# Sensors.net
KiCad netlist of a schematic drawn in Altium Designer
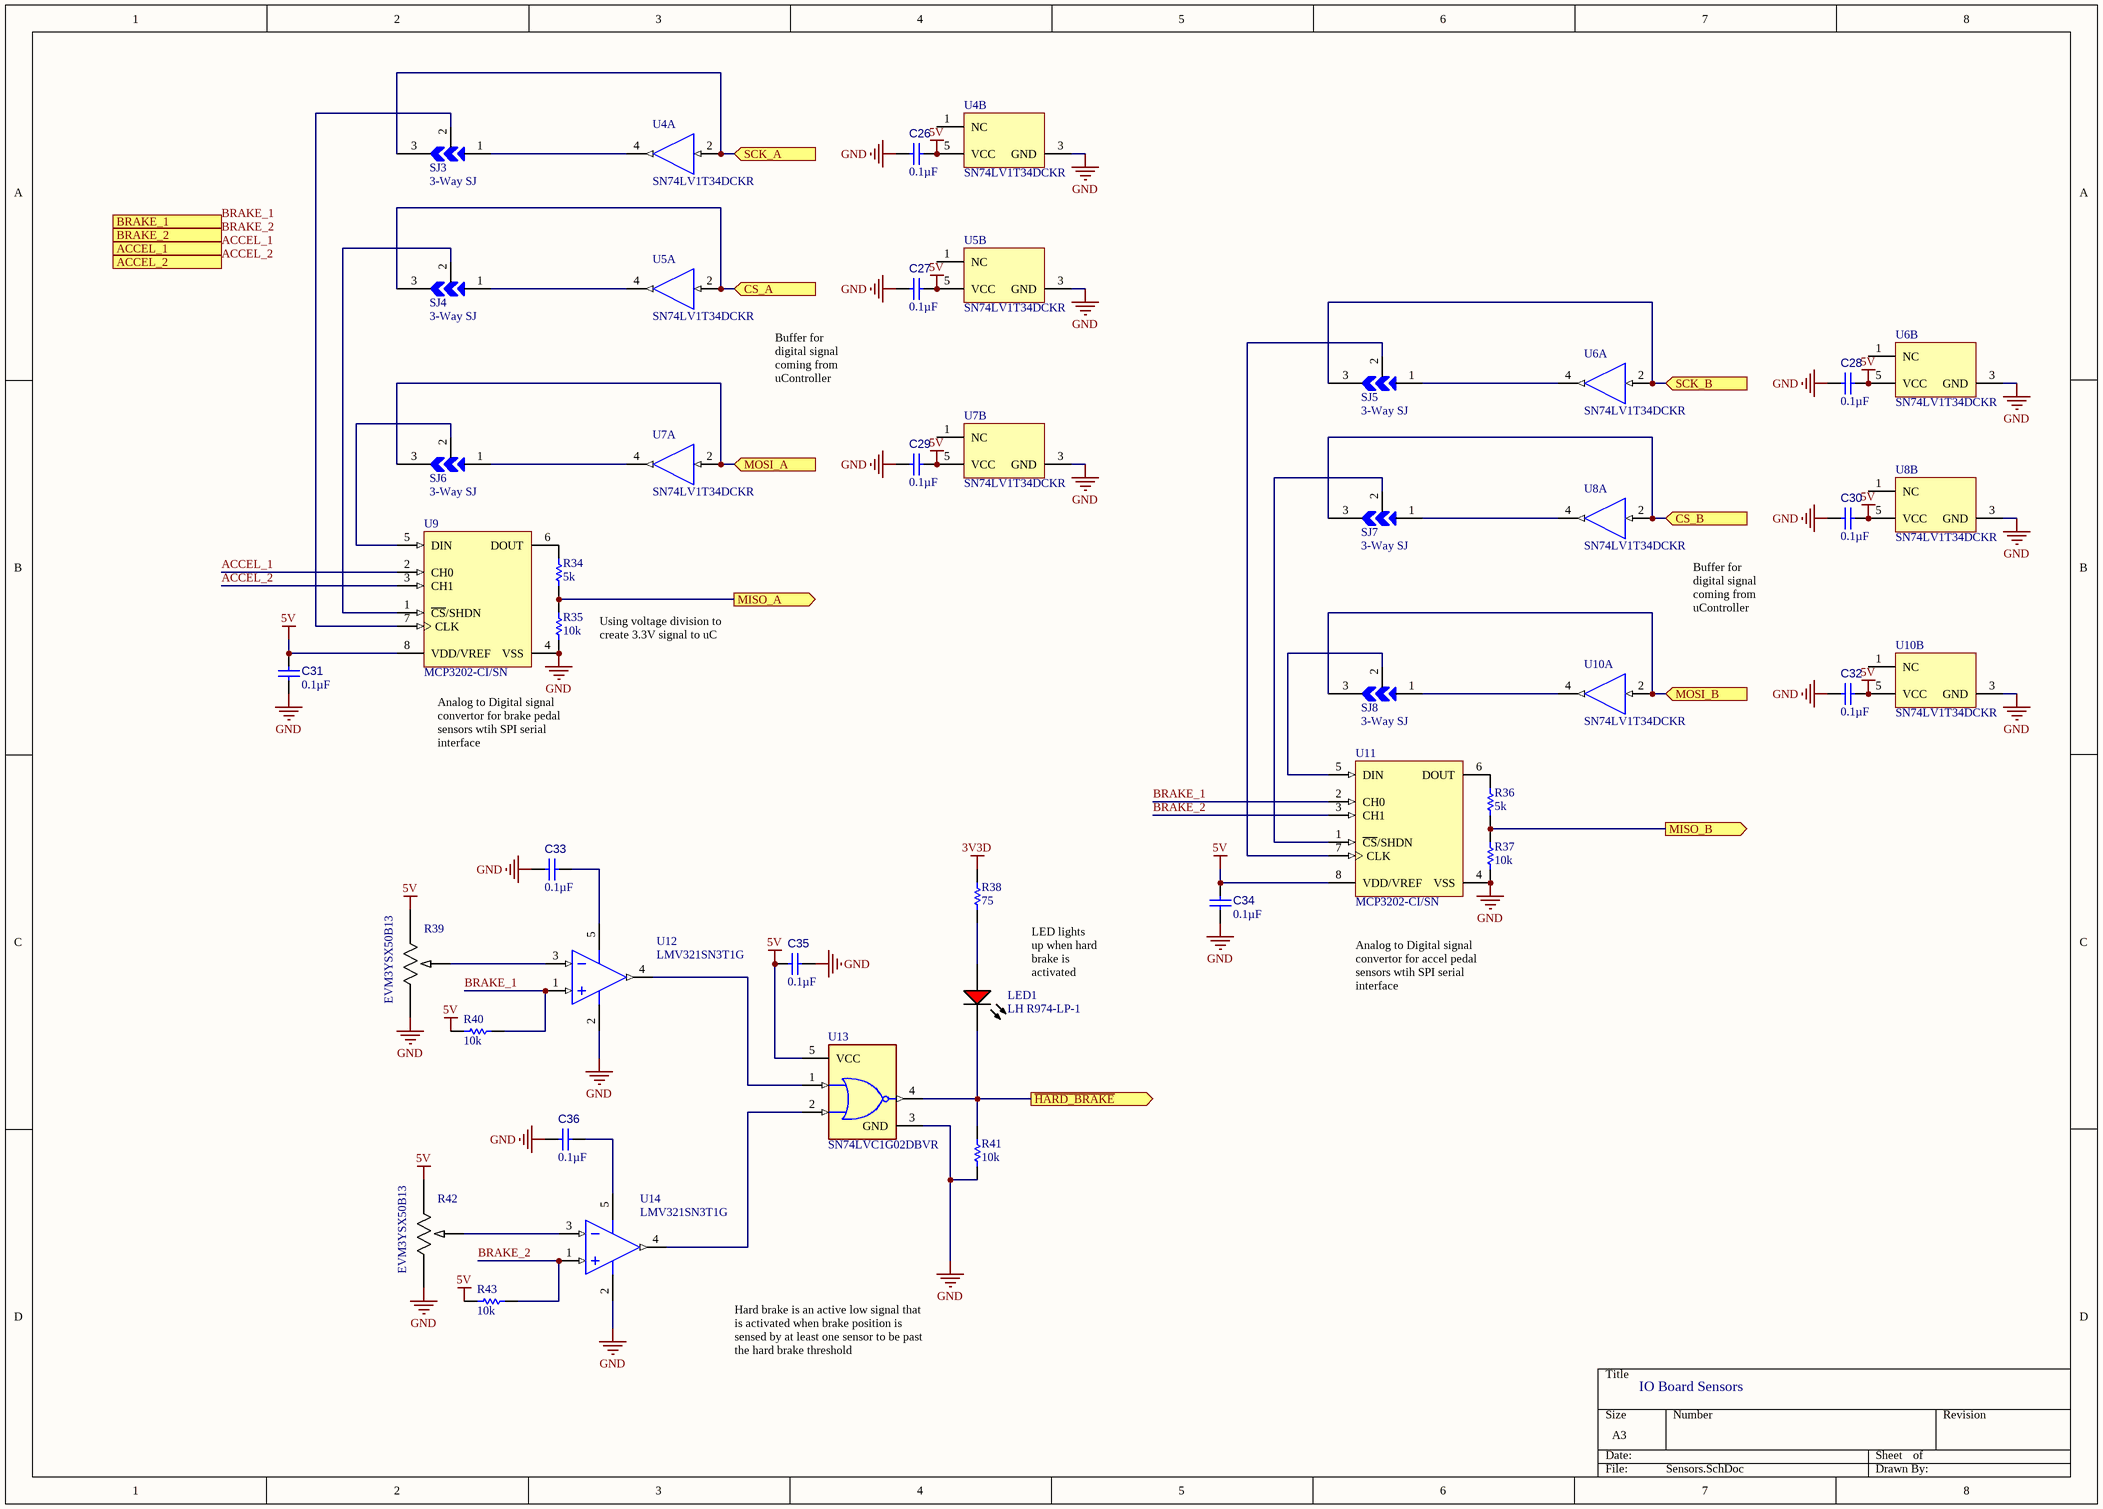
[diagram p0: Sensors.SchDoc]

(export (version "E")
  (design (tool "Eeschema 10.0.6"))
  (components
    (comp (ref "C26")
      (value "0.1µF")
      (footprint "CAPC2013X145X50ML20T25")
      (description "Chip Capacitor, 0.1 uF, +/-10%, 25 V, 0805 (2012 Metric)")
      (fields
        (field (name "MANUFACTURER") "KEMET")
        (field (name "MANUFACTURER PART NUMBER") "C0805C104K3RACTU")
      )
      (libsource (lib "Caltech FSAE") (part "CAP-NP-2"))
    )
    (comp (ref "C27")
      (value "0.1µF")
      (footprint "CAPC2013X145X50ML20T25")
      (description "Chip Capacitor, 0.1 uF, +/-10%, 25 V, 0805 (2012 Metric)")
      (fields
        (field (name "MANUFACTURER") "KEMET")
        (field (name "MANUFACTURER PART NUMBER") "C0805C104K3RACTU")
      )
      (libsource (lib "Caltech FSAE") (part "CAP-NP-2"))
    )
    (comp (ref "C28")
      (value "0.1µF")
      (footprint "CAPC2013X145X50ML20T25")
      (description "Chip Capacitor, 0.1 uF, +/-10%, 25 V, 0805 (2012 Metric)")
      (fields
        (field (name "MANUFACTURER") "KEMET")
        (field (name "MANUFACTURER PART NUMBER") "C0805C104K3RACTU")
      )
      (libsource (lib "Caltech FSAE") (part "CAP-NP-2"))
    )
    (comp (ref "C29")
      (value "0.1µF")
      (footprint "CAPC2013X145X50ML20T25")
      (description "Chip Capacitor, 0.1 uF, +/-10%, 25 V, 0805 (2012 Metric)")
      (fields
        (field (name "MANUFACTURER") "KEMET")
        (field (name "MANUFACTURER PART NUMBER") "C0805C104K3RACTU")
      )
      (libsource (lib "Caltech FSAE") (part "CAP-NP-2"))
    )
    (comp (ref "C30")
      (value "0.1µF")
      (footprint "CAPC2013X145X50ML20T25")
      (description "Chip Capacitor, 0.1 uF, +/-10%, 25 V, 0805 (2012 Metric)")
      (fields
        (field (name "MANUFACTURER") "KEMET")
        (field (name "MANUFACTURER PART NUMBER") "C0805C104K3RACTU")
      )
      (libsource (lib "Caltech FSAE") (part "CAP-NP-2"))
    )
    (comp (ref "C31")
      (value "0.1µF")
      (footprint "CAPC2013X145X50ML20T25")
      (description "Chip Capacitor, 0.1 uF, +/-10%, 25 V, 0805 (2012 Metric)")
      (fields
        (field (name "MANUFACTURER") "KEMET")
        (field (name "MANUFACTURER PART NUMBER") "C0805C104K3RACTU")
      )
      (libsource (lib "Caltech FSAE") (part "CAP-NP-2"))
    )
    (comp (ref "C32")
      (value "0.1µF")
      (footprint "CAPC2013X145X50ML20T25")
      (description "Chip Capacitor, 0.1 uF, +/-10%, 25 V, 0805 (2012 Metric)")
      (fields
        (field (name "MANUFACTURER") "KEMET")
        (field (name "MANUFACTURER PART NUMBER") "C0805C104K3RACTU")
      )
      (libsource (lib "Caltech FSAE") (part "CAP-NP-2"))
    )
    (comp (ref "C33")
      (value "0.1µF")
      (footprint "CAPC2013X145X50ML20T25")
      (description "Chip Capacitor, 0.1 uF, +/-10%, 25 V, 0805 (2012 Metric)")
      (fields
        (field (name "MANUFACTURER") "KEMET")
        (field (name "MANUFACTURER PART NUMBER") "C0805C104K3RACTU")
      )
      (libsource (lib "Caltech FSAE") (part "CAP-NP-2"))
    )
    (comp (ref "C34")
      (value "0.1µF")
      (footprint "CAPC2013X145X50ML20T25")
      (description "Chip Capacitor, 0.1 uF, +/-10%, 25 V, 0805 (2012 Metric)")
      (fields
        (field (name "MANUFACTURER") "KEMET")
        (field (name "MANUFACTURER PART NUMBER") "C0805C104K3RACTU")
      )
      (libsource (lib "Caltech FSAE") (part "CAP-NP-2"))
    )
    (comp (ref "C35")
      (value "0.1µF")
      (footprint "CAPC2013X145X50ML20T25")
      (description "Chip Capacitor, 0.1 uF, +/-10%, 25 V, 0805 (2012 Metric)")
      (fields
        (field (name "MANUFACTURER") "KEMET")
        (field (name "MANUFACTURER PART NUMBER") "C0805C104K3RACTU")
      )
      (libsource (lib "Caltech FSAE") (part "CAP-NP-2"))
    )
    (comp (ref "C36")
      (value "0.1µF")
      (footprint "CAPC2013X145X50ML20T25")
      (description "Chip Capacitor, 0.1 uF, +/-10%, 25 V, 0805 (2012 Metric)")
      (fields
        (field (name "MANUFACTURER") "KEMET")
        (field (name "MANUFACTURER PART NUMBER") "C0805C104K3RACTU")
      )
      (libsource (lib "Caltech FSAE") (part "CAP-NP-2"))
    )
    (comp (ref "LED1")
      (value "LH R974-LP-1")
      (footprint "0805_A")
      (description "LED RED DIFFUSED 0805 SMD")
      (libsource (lib "uControllerTemplate2021") (part "CMP-62016-000032-1"))
    )
    (comp (ref "R34")
      (value "5k")
      (footprint "RESC2013X50X35ML15T15")
      (description "Chip Resistor, 10k Ohm, +/- 1%, 125 mW, -55 to 155 degC, 0805 (2012 Metric)")
      (fields
        (field (name "MANUFACTURER") "Panasonic")
        (field (name "MANUFACTURER PART NUMBER") "ERA-6AEB4991V")
      )
      (libsource (lib "Caltech FSAE") (part "RES-2"))
    )
    (comp (ref "R35")
      (value "10k")
      (footprint "RESC2013X50X35ML15T15")
      (description "Chip Resistor, 10k Ohm, +/- 1%, 125 mW, -55 to 155 degC, 0805 (2012 Metric)")
      (fields
        (field (name "MANUFACTURER") "Yageo")
        (field (name "MANUFACTURER PART NUMBER") "RC0805FR-0710KL")
      )
      (libsource (lib "Caltech FSAE") (part "RES-2"))
    )
    (comp (ref "R36")
      (value "5k")
      (footprint "RESC2013X50X35ML15T15")
      (description "Chip Resistor, 10k Ohm, +/- 1%, 125 mW, -55 to 155 degC, 0805 (2012 Metric)")
      (fields
        (field (name "MANUFACTURER") "Panasonic")
        (field (name "MANUFACTURER PART NUMBER") "ERA-6AEB4991V")
      )
      (libsource (lib "Caltech FSAE") (part "RES-2"))
    )
    (comp (ref "R37")
      (value "10k")
      (footprint "RESC2013X50X35ML15T15")
      (description "Chip Resistor, 10k Ohm, +/- 1%, 125 mW, -55 to 155 degC, 0805 (2012 Metric)")
      (fields
        (field (name "MANUFACTURER") "Yageo")
        (field (name "MANUFACTURER PART NUMBER") "RC0805FR-0710KL")
      )
      (libsource (lib "Caltech FSAE") (part "RES-2"))
    )
    (comp (ref "R38")
      (value "75")
      (footprint "RESC2013X50X35ML15T15")
      (description "Chip Resistor, 10k Ohm, +/- 1%, 125 mW, -55 to 155 degC, 0805 (2012 Metric)")
      (fields
        (field (name "MANUFACTURER") "Panasonic")
        (field (name "MANUFACTURER PART NUMBER") "ERA-6AEB750V")
      )
      (libsource (lib "Caltech FSAE") (part "RES-2"))
    )
    (comp (ref "R39")
      (value "EVM3YSX50B13")
      (footprint "POT_EVM3Y_PAN")
      (description "Panasonic EVM-3YSX50B13")
      (fields (field (name "COPYRIGHT") "Copyright (C) 2018 Accelerated Designs. All rights reserved"))
      (libsource (lib "IO_Board") (part "EVM3YSX50B13"))
    )
    (comp (ref "R40")
      (value "10k")
      (footprint "RESC2013X50X35ML15T15")
      (description "Chip Resistor, 10k Ohm, +/- 1%, 125 mW, -55 to 155 degC, 0805 (2012 Metric)")
      (fields
        (field (name "MANUFACTURER") "Yageo")
        (field (name "MANUFACTURER PART NUMBER") "RC0805FR-0710KL")
      )
      (libsource (lib "Caltech FSAE") (part "RES-2"))
    )
    (comp (ref "R41")
      (value "10k")
      (footprint "RESC2013X50X35ML15T15")
      (description "Chip Resistor, 10k Ohm, +/- 1%, 125 mW, -55 to 155 degC, 0805 (2012 Metric)")
      (fields
        (field (name "MANUFACTURER") "Yageo")
        (field (name "MANUFACTURER PART NUMBER") "RC0805FR-0710KL")
      )
      (libsource (lib "Caltech FSAE") (part "RES-2"))
    )
    (comp (ref "R42")
      (value "EVM3YSX50B13")
      (footprint "POT_EVM3Y_PAN")
      (description "Panasonic EVM-3YSX50B13")
      (fields (field (name "COPYRIGHT") "Copyright (C) 2018 Accelerated Designs. All rights reserved"))
      (libsource (lib "IO_Board") (part "EVM3YSX50B13"))
    )
    (comp (ref "R43")
      (value "10k")
      (footprint "RESC2013X50X35ML15T15")
      (description "Chip Resistor, 10k Ohm, +/- 1%, 125 mW, -55 to 155 degC, 0805 (2012 Metric)")
      (fields
        (field (name "MANUFACTURER") "Yageo")
        (field (name "MANUFACTURER PART NUMBER") "RC0805FR-0710KL")
      )
      (libsource (lib "Caltech FSAE") (part "RES-2"))
    )
    (comp (ref "SJ3")
      (value "3-Way SJ")
      (footprint "3-Way SJ")
      (description "3-Way Solder Jumper")
      (libsource (lib "uControllerTemplate2021") (part "3-Way SJ"))
    )
    (comp (ref "SJ4")
      (value "3-Way SJ")
      (footprint "3-Way SJ")
      (description "3-Way Solder Jumper")
      (libsource (lib "uControllerTemplate2021") (part "3-Way SJ"))
    )
    (comp (ref "SJ5")
      (value "3-Way SJ")
      (footprint "3-Way SJ")
      (description "3-Way Solder Jumper")
      (libsource (lib "uControllerTemplate2021") (part "3-Way SJ"))
    )
    (comp (ref "SJ6")
      (value "3-Way SJ")
      (footprint "3-Way SJ")
      (description "3-Way Solder Jumper")
      (libsource (lib "uControllerTemplate2021") (part "3-Way SJ"))
    )
    (comp (ref "SJ7")
      (value "3-Way SJ")
      (footprint "3-Way SJ")
      (description "3-Way Solder Jumper")
      (libsource (lib "uControllerTemplate2021") (part "3-Way SJ"))
    )
    (comp (ref "SJ8")
      (value "3-Way SJ")
      (footprint "3-Way SJ")
      (description "3-Way Solder Jumper")
      (libsource (lib "uControllerTemplate2021") (part "3-Way SJ"))
    )
    (comp (ref "U4")
      (value "SN74LV1T34DCKR")
      (footprint "DCK0005A_L")
      (description "Single Power Supply BUFFER Logic Level Shifter (no enable), DCK0005A, LARGE T&R")
      (fields
        (field (name "MANUFACTURER") "Texas Instruments")
        (field (name "GENERIC PART NUMBER") "SN74LV1T34")
      )
      (libsource (lib "Altium Content Vault") (part "TI-SN74XXX1XXX-XX-5"))
    )
    (comp (ref "U5")
      (value "SN74LV1T34DCKR")
      (footprint "DCK0005A_L")
      (description "Single Power Supply BUFFER Logic Level Shifter (no enable), DCK0005A, LARGE T&R")
      (fields
        (field (name "MANUFACTURER") "Texas Instruments")
        (field (name "GENERIC PART NUMBER") "SN74LV1T34")
      )
      (libsource (lib "Altium Content Vault") (part "TI-SN74XXX1XXX-XX-5"))
    )
    (comp (ref "U6")
      (value "SN74LV1T34DCKR")
      (footprint "DCK0005A_L")
      (description "Single Power Supply BUFFER Logic Level Shifter (no enable), DCK0005A, LARGE T&R")
      (fields
        (field (name "MANUFACTURER") "Texas Instruments")
        (field (name "GENERIC PART NUMBER") "SN74LV1T34")
      )
      (libsource (lib "") (part "TI-SN74XXX1XXX-XX-5_1"))
    )
    (comp (ref "U7")
      (value "SN74LV1T34DCKR")
      (footprint "DCK0005A_L")
      (description "Single Power Supply BUFFER Logic Level Shifter (no enable), DCK0005A, LARGE T&R")
      (fields
        (field (name "MANUFACTURER") "Texas Instruments")
        (field (name "GENERIC PART NUMBER") "SN74LV1T34")
      )
      (libsource (lib "") (part "TI-SN74XXX1XXX-XX-5_1"))
    )
    (comp (ref "U8")
      (value "SN74LV1T34DCKR")
      (footprint "DCK0005A_L")
      (description "Single Power Supply BUFFER Logic Level Shifter (no enable), DCK0005A, LARGE T&R")
      (fields
        (field (name "MANUFACTURER") "Texas Instruments")
        (field (name "GENERIC PART NUMBER") "SN74LV1T34")
      )
      (libsource (lib "Altium Content Vault") (part "TI-SN74XXX1XXX-XX-5"))
    )
    (comp (ref "U9")
      (value "MCP3202-CI/SN")
      (footprint "SOIC-SN8_L")
      (libsource (lib "Altium Content Vault") (part "CON-ADC-MCP3002-8"))
    )
    (comp (ref "U10")
      (value "SN74LV1T34DCKR")
      (footprint "DCK0005A_L")
      (description "Single Power Supply BUFFER Logic Level Shifter (no enable), DCK0005A, LARGE T&R")
      (fields
        (field (name "MANUFACTURER") "Texas Instruments")
        (field (name "GENERIC PART NUMBER") "SN74LV1T34")
      )
      (libsource (lib "Altium Content Vault") (part "TI-SN74XXX1XXX-XX-5"))
    )
    (comp (ref "U11")
      (value "MCP3202-CI/SN")
      (footprint "SOIC-SN8_L")
      (libsource (lib "Altium Content Vault") (part "CON-ADC-MCP3002-8"))
    )
    (comp (ref "U12")
      (value "LMV321SN3T1G")
      (footprint "ONSC-TSOP-5-483-02_V")
      (fields (field (name "MANUFACTURER") "On Semiconductor"))
      (libsource (lib "Altium Content Vault") (part "ONSC-LMV321-TSOP-5-483-02"))
    )
    (comp (ref "U13")
      (value "SN74LVC1G02DBVR")
      (footprint "FP-DBV0005A-MFG")
      (description "IC GATE NOR 1CH 2-INP SOT23-5")
      (fields
        (field (name "OCTOPART") "https://octopart.com/sn74lvc1g02dbvr-texas+instruments-464409")
        (field (name "MANUFACTURER") "Texas Instruments")
      )
      (libsource (lib "Altium Content Vault") (part "8be38c0101a6f76b12a6e3a542e29a9"))
    )
    (comp (ref "U14")
      (value "LMV321SN3T1G")
      (footprint "ONSC-TSOP-5-483-02_V")
      (fields (field (name "MANUFACTURER") "On Semiconductor"))
      (libsource (lib "Altium Content Vault") (part "ONSC-LMV321-TSOP-5-483-02"))
    )
  )
  (nets
    (net (code "1") (name "/ACCEL_1") (class "Default")
      (node (ref "U9") (pin "2") (pinfunction "CH0_2") (pintype "input"))
    )
    (net (code "2") (name "/ACCEL_2") (class "Default")
      (node (ref "U9") (pin "3") (pinfunction "CH1_3") (pintype "input"))
    )
    (net (code "3") (name "/BRAKE_1") (class "Default")
      (node (ref "R40") (pin "1") (pinfunction "1_1") (pintype "passive"))
      (node (ref "U11") (pin "2") (pinfunction "CH0_2") (pintype "input"))
      (node (ref "U12") (pin "1") (pinfunction "IN+_1") (pintype "input"))
    )
    (net (code "4") (name "/BRAKE_2") (class "Default")
      (node (ref "R43") (pin "1") (pinfunction "1_1") (pintype "passive"))
      (node (ref "U11") (pin "3") (pinfunction "CH1_3") (pintype "input"))
      (node (ref "U14") (pin "1") (pinfunction "IN+_1") (pintype "input"))
    )
    (net (code "5") (name "/CS_A") (class "Default")
      (node (ref "SJ4") (pin "3") (pinfunction "3_3") (pintype "passive"))
      (node (ref "U5") (pin "2") (pinfunction "A_2") (pintype "input"))
    )
    (net (code "6") (name "/CS_B") (class "Default")
      (node (ref "SJ7") (pin "3") (pinfunction "3_3") (pintype "passive"))
      (node (ref "U8") (pin "2") (pinfunction "A_2") (pintype "input"))
    )
    (net (code "7") (name "/MISO_A") (class "Default")
      (node (ref "R34") (pin "2") (pinfunction "2_2") (pintype "passive"))
      (node (ref "R35") (pin "2") (pinfunction "2_2") (pintype "passive"))
    )
    (net (code "8") (name "/MISO_B") (class "Default")
      (node (ref "R36") (pin "2") (pinfunction "2_2") (pintype "passive"))
      (node (ref "R37") (pin "2") (pinfunction "2_2") (pintype "passive"))
    )
    (net (code "9") (name "/MOSI_A") (class "Default")
      (node (ref "SJ6") (pin "3") (pinfunction "3_3") (pintype "passive"))
      (node (ref "U7") (pin "2") (pinfunction "A_2") (pintype "input"))
    )
    (net (code "10") (name "/MOSI_B") (class "Default")
      (node (ref "SJ8") (pin "3") (pinfunction "3_3") (pintype "passive"))
      (node (ref "U10") (pin "2") (pinfunction "A_2") (pintype "input"))
    )
    (net (code "11") (name "/SCK_A") (class "Default")
      (node (ref "SJ3") (pin "3") (pinfunction "3_3") (pintype "passive"))
      (node (ref "U4") (pin "2") (pinfunction "A_2") (pintype "input"))
    )
    (net (code "12") (name "/SCK_B") (class "Default")
      (node (ref "SJ5") (pin "3") (pinfunction "3_3") (pintype "passive"))
      (node (ref "U6") (pin "2") (pinfunction "A_2") (pintype "input"))
    )
    (net (code "13") (name "/~{HARD_BRAKE}") (class "Default")
      (node (ref "LED1") (pin "1") (pinfunction "K_1") (pintype "passive"))
      (node (ref "R41") (pin "2") (pinfunction "2_2") (pintype "passive"))
      (node (ref "U13") (pin "4") (pinfunction "Y_4") (pintype "output"))
    )
    (net (code "14") (name "3V3D") (class "Default")
      (node (ref "R38") (pin "1") (pinfunction "1_1") (pintype "passive"))
    )
    (net (code "15") (name "5V") (class "Default")
      (node (ref "C26") (pin "1") (pinfunction "1_1") (pintype "passive"))
      (node (ref "C27") (pin "1") (pinfunction "1_1") (pintype "passive"))
      (node (ref "C28") (pin "1") (pinfunction "1_1") (pintype "passive"))
      (node (ref "C29") (pin "1") (pinfunction "1_1") (pintype "passive"))
      (node (ref "C30") (pin "1") (pinfunction "1_1") (pintype "passive"))
      (node (ref "C31") (pin "2") (pinfunction "2_2") (pintype "passive"))
      (node (ref "C32") (pin "1") (pinfunction "1_1") (pintype "passive"))
      (node (ref "C34") (pin "2") (pinfunction "2_2") (pintype "passive"))
      (node (ref "C35") (pin "2") (pinfunction "2_2") (pintype "passive"))
      (node (ref "R39") (pin "1") (pinfunction "1_1") (pintype "passive"))
      (node (ref "R40") (pin "2") (pinfunction "2_2") (pintype "passive"))
      (node (ref "R42") (pin "1") (pinfunction "1_1") (pintype "passive"))
      (node (ref "R43") (pin "2") (pinfunction "2_2") (pintype "passive"))
      (node (ref "U10") (pin "5") (pinfunction "VCC_5") (pintype "power_in"))
      (node (ref "U11") (pin "8") (pinfunction "VDD/VREF_8") (pintype "power_in"))
      (node (ref "U13") (pin "5") (pinfunction "VCC_5") (pintype "power_in"))
      (node (ref "U4") (pin "5") (pinfunction "VCC_5") (pintype "power_in"))
      (node (ref "U5") (pin "5") (pinfunction "VCC_5") (pintype "power_in"))
      (node (ref "U6") (pin "5") (pinfunction "VCC_5") (pintype "power_in"))
      (node (ref "U7") (pin "5") (pinfunction "VCC_5") (pintype "power_in"))
      (node (ref "U8") (pin "5") (pinfunction "VCC_5") (pintype "power_in"))
      (node (ref "U9") (pin "8") (pinfunction "VDD/VREF_8") (pintype "power_in"))
    )
    (net (code "16") (name "GND") (class "Default")
      (node (ref "C26") (pin "2") (pinfunction "2_2") (pintype "passive"))
      (node (ref "C27") (pin "2") (pinfunction "2_2") (pintype "passive"))
      (node (ref "C28") (pin "2") (pinfunction "2_2") (pintype "passive"))
      (node (ref "C29") (pin "2") (pinfunction "2_2") (pintype "passive"))
      (node (ref "C30") (pin "2") (pinfunction "2_2") (pintype "passive"))
      (node (ref "C31") (pin "1") (pinfunction "1_1") (pintype "passive"))
      (node (ref "C32") (pin "2") (pinfunction "2_2") (pintype "passive"))
      (node (ref "C33") (pin "2") (pinfunction "2_2") (pintype "passive"))
      (node (ref "C34") (pin "1") (pinfunction "1_1") (pintype "passive"))
      (node (ref "C35") (pin "1") (pinfunction "1_1") (pintype "passive"))
      (node (ref "C36") (pin "2") (pinfunction "2_2") (pintype "passive"))
      (node (ref "R35") (pin "1") (pinfunction "1_1") (pintype "passive"))
      (node (ref "R37") (pin "1") (pinfunction "1_1") (pintype "passive"))
      (node (ref "R39") (pin "3") (pinfunction "3_3") (pintype "passive"))
      (node (ref "R41") (pin "1") (pinfunction "1_1") (pintype "passive"))
      (node (ref "R42") (pin "3") (pinfunction "3_3") (pintype "passive"))
      (node (ref "U10") (pin "3") (pinfunction "GND_3") (pintype "power_in"))
      (node (ref "U11") (pin "4") (pinfunction "VSS_4") (pintype "power_in"))
      (node (ref "U12") (pin "2") (pinfunction "V-_2") (pintype "power_in"))
      (node (ref "U13") (pin "3") (pinfunction "GND_3") (pintype "power_in"))
      (node (ref "U14") (pin "2") (pinfunction "V-_2") (pintype "power_in"))
      (node (ref "U4") (pin "3") (pinfunction "GND_3") (pintype "power_in"))
      (node (ref "U5") (pin "3") (pinfunction "GND_3") (pintype "power_in"))
      (node (ref "U6") (pin "3") (pinfunction "GND_3") (pintype "power_in"))
      (node (ref "U7") (pin "3") (pinfunction "GND_3") (pintype "power_in"))
      (node (ref "U8") (pin "3") (pinfunction "GND_3") (pintype "power_in"))
      (node (ref "U9") (pin "4") (pinfunction "VSS_4") (pintype "power_in"))
    )
    (net (code "17") (name "Net-(LED1-A)") (class "Default")
      (node (ref "LED1") (pin "2") (pinfunction "A_2") (pintype "passive"))
      (node (ref "R38") (pin "2") (pinfunction "2_2") (pintype "passive"))
    )
    (net (code "18") (name "Net-(U4A-Y)") (class "Default")
      (node (ref "SJ3") (pin "1") (pinfunction "1_1") (pintype "passive"))
      (node (ref "U4") (pin "4") (pinfunction "Y_4") (pintype "output"))
    )
    (net (code "19") (name "Net-(U5A-Y)") (class "Default")
      (node (ref "SJ4") (pin "1") (pinfunction "1_1") (pintype "passive"))
      (node (ref "U5") (pin "4") (pinfunction "Y_4") (pintype "output"))
    )
    (net (code "20") (name "Net-(U6A-Y)") (class "Default")
      (node (ref "SJ5") (pin "1") (pinfunction "1_1") (pintype "passive"))
      (node (ref "U6") (pin "4") (pinfunction "Y_4") (pintype "output"))
    )
    (net (code "21") (name "Net-(U7A-Y)") (class "Default")
      (node (ref "SJ6") (pin "1") (pinfunction "1_1") (pintype "passive"))
      (node (ref "U7") (pin "4") (pinfunction "Y_4") (pintype "output"))
    )
    (net (code "22") (name "Net-(U8A-Y)") (class "Default")
      (node (ref "SJ7") (pin "1") (pinfunction "1_1") (pintype "passive"))
      (node (ref "U8") (pin "4") (pinfunction "Y_4") (pintype "output"))
    )
    (net (code "23") (name "Net-(U9-CLK)") (class "Default")
      (node (ref "SJ3") (pin "2") (pinfunction "2_2") (pintype "passive"))
      (node (ref "U9") (pin "7") (pinfunction "CLK_7") (pintype "input"))
    )
    (net (code "24") (name "Net-(U9-DIN)") (class "Default")
      (node (ref "SJ6") (pin "2") (pinfunction "2_2") (pintype "passive"))
      (node (ref "U9") (pin "5") (pinfunction "DIN_5") (pintype "input"))
    )
    (net (code "25") (name "Net-(U9-DOUT)") (class "Default")
      (node (ref "R34") (pin "1") (pinfunction "1_1") (pintype "passive"))
      (node (ref "U9") (pin "6") (pinfunction "DOUT_6") (pintype "tri_state"))
    )
    (net (code "26") (name "Net-(U9-~{CS}{slash}SHDN)") (class "Default")
      (node (ref "SJ4") (pin "2") (pinfunction "2_2") (pintype "passive"))
      (node (ref "U9") (pin "1") (pinfunction "~{CS}/SHDN_1") (pintype "input"))
    )
    (net (code "27") (name "Net-(U10A-Y)") (class "Default")
      (node (ref "SJ8") (pin "1") (pinfunction "1_1") (pintype "passive"))
      (node (ref "U10") (pin "4") (pinfunction "Y_4") (pintype "output"))
    )
    (net (code "28") (name "Net-(U11-CLK)") (class "Default")
      (node (ref "SJ5") (pin "2") (pinfunction "2_2") (pintype "passive"))
      (node (ref "U11") (pin "7") (pinfunction "CLK_7") (pintype "input"))
    )
    (net (code "29") (name "Net-(U11-DIN)") (class "Default")
      (node (ref "SJ8") (pin "2") (pinfunction "2_2") (pintype "passive"))
      (node (ref "U11") (pin "5") (pinfunction "DIN_5") (pintype "input"))
    )
    (net (code "30") (name "Net-(U11-DOUT)") (class "Default")
      (node (ref "R36") (pin "1") (pinfunction "1_1") (pintype "passive"))
      (node (ref "U11") (pin "6") (pinfunction "DOUT_6") (pintype "tri_state"))
    )
    (net (code "31") (name "Net-(U11-~{CS}{slash}SHDN)") (class "Default")
      (node (ref "SJ7") (pin "2") (pinfunction "2_2") (pintype "passive"))
      (node (ref "U11") (pin "1") (pinfunction "~{CS}/SHDN_1") (pintype "input"))
    )
    (net (code "32") (name "Net-(U12-IN-)") (class "Default")
      (node (ref "R39") (pin "2") (pinfunction "2_2") (pintype "passive"))
      (node (ref "U12") (pin "3") (pinfunction "IN-_3") (pintype "input"))
    )
    (net (code "33") (name "Net-(U12-OUT)") (class "Default")
      (node (ref "U12") (pin "4") (pinfunction "OUT_4") (pintype "output"))
      (node (ref "U13") (pin "1") (pinfunction "A_1") (pintype "input"))
    )
    (net (code "34") (name "Net-(U12-V+)") (class "Default")
      (node (ref "C33") (pin "1") (pinfunction "1_1") (pintype "passive"))
      (node (ref "U12") (pin "5") (pinfunction "V+_5") (pintype "power_in"))
    )
    (net (code "35") (name "Net-(U13-B)") (class "Default")
      (node (ref "U13") (pin "2") (pinfunction "B_2") (pintype "input"))
      (node (ref "U14") (pin "4") (pinfunction "OUT_4") (pintype "output"))
    )
    (net (code "36") (name "Net-(U14-IN-)") (class "Default")
      (node (ref "R42") (pin "2") (pinfunction "2_2") (pintype "passive"))
      (node (ref "U14") (pin "3") (pinfunction "IN-_3") (pintype "input"))
    )
    (net (code "37") (name "Net-(U14-V+)") (class "Default")
      (node (ref "C36") (pin "1") (pinfunction "1_1") (pintype "passive"))
      (node (ref "U14") (pin "5") (pinfunction "V+_5") (pintype "power_in"))
    )
    (net (code "38") (name "unconnected-(U4B-NC-Pad1)") (class "Default")
      (node (ref "U4") (pin "1") (pinfunction "NC_1") (pintype "passive"))
    )
    (net (code "39") (name "unconnected-(U5B-NC-Pad1)") (class "Default")
      (node (ref "U5") (pin "1") (pinfunction "NC_1") (pintype "passive"))
    )
    (net (code "40") (name "unconnected-(U6B-NC-Pad1)") (class "Default")
      (node (ref "U6") (pin "1") (pinfunction "NC_1") (pintype "passive"))
    )
    (net (code "41") (name "unconnected-(U7B-NC-Pad1)") (class "Default")
      (node (ref "U7") (pin "1") (pinfunction "NC_1") (pintype "passive"))
    )
    (net (code "42") (name "unconnected-(U8B-NC-Pad1)") (class "Default")
      (node (ref "U8") (pin "1") (pinfunction "NC_1") (pintype "passive"))
    )
    (net (code "43") (name "unconnected-(U10B-NC-Pad1)") (class "Default")
      (node (ref "U10") (pin "1") (pinfunction "NC_1") (pintype "passive"))
    )
  )
)
